# 07-NCP3066_LCD.net
KiCad netlist of a schematic drawn in Altium Designer
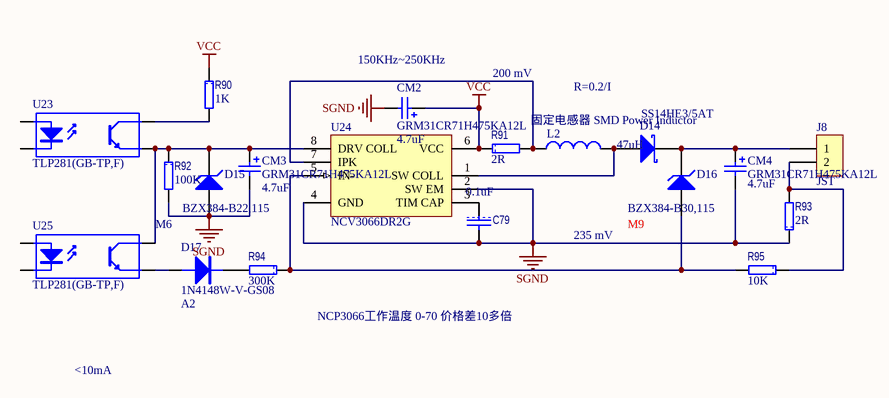
[diagram p0: 07-NCP3066_LCD背光.SchDoc]

(export (version "E")
  (design (tool "Eeschema 10.0.6"))
  (components
    (comp (ref "C79")
      (value "0.1uF")
      (footprint "1608[0603]C")
      (description "多层陶瓷电容器MLCC - SMD/SMT 0603 0.1uF 50volts X7R 10%")
      (fields (field (name "MANUFACTURER") "TDK") (field (name "MANUFACTURER PART NUMBER") "C1608X7R1H104K"))
      (libsource (lib "*") (part "CAP"))
    )
    (comp (ref "CM2")
      (value "GRM31CR71H475KA12L")
      (footprint "3216[1206]C")
      (description "多层陶瓷电容器MLCC - SMD/SMT 4.7uF 50Volts 10%")
      (fields (field (name "MANUFACTURER") "Murata Electronics") (field (name "ALTIUM_VALUE") "4.7uF"))
      (libsource (lib "Miscellaneous Devices") (part "Cap Pol2"))
    )
    (comp (ref "CM3")
      (value "GRM31CR71H475KA12L")
      (footprint "3216[1206]C")
      (description "多层陶瓷电容器MLCC - SMD/SMT 4.7uF 50Volts 10%")
      (fields (field (name "MANUFACTURER") "Murata Electronics") (field (name "ALTIUM_VALUE") "4.7uF"))
      (libsource (lib "Miscellaneous Devices") (part "Cap Pol2"))
    )
    (comp (ref "CM4")
      (value "GRM31CR71H475KA12L")
      (footprint "3216[1206]C")
      (description "多层陶瓷电容器MLCC - SMD/SMT 4.7uF 50Volts 10%")
      (fields (field (name "MANUFACTURER") "Murata Electronics") (field (name "ALTIUM_VALUE") "4.7uF"))
      (libsource (lib "Miscellaneous Devices") (part "Cap Pol2"))
    )
    (comp (ref "D14")
      (value "SS14HE3/5AT")
      (footprint "DO-214AC/SMA")
      (description "肖特基二极管与整流器 40 Volt 1.0 Amp 40 Amp IFSM")
      (fields (field (name "MANUFACTURER") "Vishay Semiconductors"))
      (libsource (lib "IR Rectifier - Schottky") (part "10BQ060"))
    )
    (comp (ref "D15")
      (value "BZX384-B22,115")
      (footprint "SOD323")
      (description "稳压二极管 DIODE ZENER 2 PCT")
      (fields (field (name "MANUFACTURER") "NXP Semiconductors") (field (name "ALTIUM_VALUE") "M6"))
      (libsource (lib "Miscellaneous Devices") (part "D Zener"))
    )
    (comp (ref "D16")
      (value "BZX384-B30,115")
      (footprint "SOD323")
      (description "稳压二极管 DIODE ZENER 2 PCT")
      (fields (field (name "MANUFACTURER") "NXP Semiconductors") (field (name "ALTIUM_VALUE") "M9"))
      (libsource (lib "Miscellaneous Devices") (part "D Zener"))
    )
    (comp (ref "D17")
      (value "1N4148W-V-GS08")
      (footprint "SOD323")
      (description "二极管 - 通用，功率，开关 100V Io/150mA")
      (fields (field (name "MANUFACTURER") "Vishay Semiconductors") (field (name "ALTIUM_VALUE") "A2"))
      (libsource (lib "IN4148") (part "1N4148W"))
    )
    (comp (ref "J8") (value "JST") (footprint "JST") (description "CON") (libsource (lib "*") (part "CON2")))
    (comp (ref "L2")
      (value "47uH")
      (footprint "INDP5050X28N")
      (description "固定电感器 SMD Power Inductor")
      (fields
        (field (name "MANUFACTURER") "Sumida")
        (field (name "MANUFACTURER PART NUMBER") "CDRH5D28RH125NP-470MC")
        (field (name "DESCRIPTION 1") "固定电感器 SMD Power Inductor")
      )
      (libsource (lib "Miscellaneous Devices") (part "Inductor"))
    )
    (comp (ref "R90")
      (value "1K")
      (footprint "1608[0603]R")
      (description "厚膜电阻器 - SMD 1/10watt 1.0Kohms 1%")
      (fields
        (field (name "MANUFACTURER") "Vishay / Dale")
        (field (name "MANUFACTURER PART NUMBER") "CRCW06031K00FKEA")
      )
      (libsource (lib "1K 1%") (part "RES"))
    )
    (comp (ref "R91")
      (value "2R")
      (footprint "1608[0603]R")
      (description "厚膜电阻器 - SMD 1/10watt 2ohms 1%")
      (fields
        (field (name "MANUFACTURER") "Vishay / Dale")
        (field (name "MANUFACTURER PART NUMBER") "CRCW06032R00FKEA")
      )
      (libsource (lib "2R 1%") (part "RES"))
    )
    (comp (ref "R92")
      (value "100K")
      (footprint "1608[0603]R")
      (description "厚膜电阻器 - SMD 1/10watt 100Kohms 1%")
      (fields
        (field (name "MANUFACTURER") "Vishay / Dale")
        (field (name "MANUFACTURER PART NUMBER") "CRCW0603100KFKEA")
      )
      (libsource (lib "100K 1%") (part "RES"))
    )
    (comp (ref "R93")
      (value "2R")
      (footprint "1608[0603]R")
      (description "厚膜电阻器 - SMD 1/10watt 2ohms 1%")
      (fields
        (field (name "MANUFACTURER") "Vishay / Dale")
        (field (name "MANUFACTURER PART NUMBER") "CRCW06032R00FKEA")
      )
      (libsource (lib "2R 1%") (part "RES"))
    )
    (comp (ref "R94")
      (value "300K")
      (footprint "1608[0603]R")
      (description "厚膜电阻器 - SMD 1/10watt 300Kohms 1%")
      (fields
        (field (name "MANUFACTURER") "Vishay / Dale")
        (field (name "MANUFACTURER PART NUMBER") "CRCW0603300KFKEA")
      )
      (libsource (lib "300K 1%") (part "RES"))
    )
    (comp (ref "R95")
      (value "10K")
      (footprint "1608[0603]R")
      (description "厚膜电阻器 - SMD 1/10watt 10Kohms 1%")
      (fields
        (field (name "MANUFACTURER") "Vishay / Dale")
        (field (name "MANUFACTURER PART NUMBER") "CRCW060310K0FKEA")
      )
      (libsource (lib "10K 1%") (part "RES"))
    )
    (comp (ref "U23")
      (value "TLP281(GB-TP,F)")
      (footprint "SSOP4_N")
      (description "晶体管输出光电耦合器 80Vceo 2500Vrms standard")
      (fields (field (name "MANUFACTURER") "Toshiba"))
      (libsource (lib "Miscellaneous Devices") (part "Optoisolator1"))
    )
    (comp (ref "U24")
      (value "NCV3066DR2G")
      (footprint "SOIC8_N")
      (description "IC LED DRIVER HIGH BRIGHT 8-SOIC")
      (fields (field (name "MANUFACTURER") "ON Semiconductor"))
      (libsource (lib "ON Semi Power Mgt DC-DC Converter") (part "MC33063AD"))
    )
    (comp (ref "U25")
      (value "TLP281(GB-TP,F)")
      (footprint "SSOP4_N")
      (description "晶体管输出光电耦合器 80Vceo 2500Vrms standard")
      (fields (field (name "MANUFACTURER") "Toshiba"))
      (libsource (lib "Miscellaneous Devices") (part "Optoisolator1"))
    )
  )
  (nets
    (net (code "1") (name "Net-(D14-A)") (class "Default")
      (node (ref "D14") (pin "1") (pinfunction "A_1") (pintype "passive"))
      (node (ref "L2") (pin "2") (pinfunction "2_2") (pintype "passive"))
      (node (ref "U24") (pin "1") (pinfunction "SW_COLL_1") (pintype "passive"))
    )
    (net (code "2") (name "Net-(D14-K)") (class "Default")
      (node (ref "CM4") (pin "1") (pinfunction "1_1") (pintype "passive"))
      (node (ref "D14") (pin "2") (pinfunction "K_2") (pintype "passive"))
      (node (ref "D16") (pin "2") (pinfunction "K_2") (pintype "passive"))
      (node (ref "J8") (pin "1") (pinfunction "1_1") (pintype "passive"))
    )
    (net (code "3") (name "Net-(D15-K)") (class "Default")
      (node (ref "CM3") (pin "1") (pinfunction "1_1") (pintype "passive"))
      (node (ref "D15") (pin "2") (pinfunction "K_2") (pintype "passive"))
      (node (ref "R92") (pin "1") (pinfunction "1_1") (pintype "passive"))
      (node (ref "U23") (pin "3") (pinfunction "E_3") (pintype "passive"))
      (node (ref "U24") (pin "8") (pinfunction "DRV_COLL_8") (pintype "open_collector"))
      (node (ref "U25") (pin "4") (pinfunction "C_4") (pintype "passive"))
    )
    (net (code "4") (name "Net-(D16-A)") (class "Default")
      (node (ref "D16") (pin "1") (pinfunction "A_1") (pintype "passive"))
      (node (ref "R94") (pin "1") (pinfunction "1_1") (pintype "passive"))
      (node (ref "R95") (pin "2") (pinfunction "2_2") (pintype "passive"))
      (node (ref "U24") (pin "5") (pinfunction "IN-_5") (pintype "input"))
    )
    (net (code "5") (name "Net-(D17-A)") (class "Default")
      (node (ref "D17") (pin "1") (pinfunction "A_1") (pintype "passive"))
      (node (ref "U25") (pin "3") (pinfunction "E_3") (pintype "passive"))
    )
    (net (code "6") (name "Net-(D17-K)") (class "Default")
      (node (ref "D17") (pin "2") (pinfunction "K_2") (pintype "passive"))
      (node (ref "R94") (pin "2") (pinfunction "2_2") (pintype "passive"))
    )
    (net (code "7") (name "Net-(J8-Pad2)") (class "Default")
      (node (ref "J8") (pin "2") (pinfunction "2_2") (pintype "passive"))
      (node (ref "R93") (pin "2") (pinfunction "2_2") (pintype "passive"))
      (node (ref "R95") (pin "1") (pinfunction "1_1") (pintype "passive"))
    )
    (net (code "8") (name "Net-(U23-C)") (class "Default")
      (node (ref "R90") (pin "2") (pinfunction "2_2") (pintype "passive"))
      (node (ref "U23") (pin "4") (pinfunction "C_4") (pintype "passive"))
    )
    (net (code "9") (name "Net-(U24-IPK)") (class "Default")
      (node (ref "L2") (pin "1") (pinfunction "1_1") (pintype "passive"))
      (node (ref "R91") (pin "2") (pinfunction "2_2") (pintype "passive"))
      (node (ref "U24") (pin "7") (pinfunction "IPK_7") (pintype "passive"))
    )
    (net (code "10") (name "Net-(U24-TIM_CAP)") (class "Default")
      (node (ref "C79") (pin "1") (pinfunction "1_1") (pintype "passive"))
      (node (ref "U24") (pin "3") (pinfunction "TIM_CAP_3") (pintype "passive"))
    )
    (net (code "11") (name "SGND") (class "Default")
      (node (ref "C79") (pin "2") (pinfunction "2_2") (pintype "passive"))
      (node (ref "CM2") (pin "2") (pinfunction "2_2") (pintype "passive"))
      (node (ref "CM3") (pin "2") (pinfunction "2_2") (pintype "passive"))
      (node (ref "CM4") (pin "2") (pinfunction "2_2") (pintype "passive"))
      (node (ref "D15") (pin "1") (pinfunction "A_1") (pintype "passive"))
      (node (ref "R92") (pin "2") (pinfunction "2_2") (pintype "passive"))
      (node (ref "R93") (pin "1") (pinfunction "1_1") (pintype "passive"))
      (node (ref "U24") (pin "2") (pinfunction "SW_EM_2") (pintype "passive"))
      (node (ref "U24") (pin "4") (pinfunction "GND_4") (pintype "power_in"))
    )
    (net (code "12") (name "VCC") (class "Default")
      (node (ref "CM2") (pin "1") (pinfunction "1_1") (pintype "passive"))
      (node (ref "R90") (pin "1") (pinfunction "1_1") (pintype "passive"))
      (node (ref "R91") (pin "1") (pinfunction "1_1") (pintype "passive"))
      (node (ref "U24") (pin "6") (pinfunction "VCC_6") (pintype "power_in"))
    )
    (net (code "13") (name "unconnected-(U23-A-Pad1)") (class "Default")
      (node (ref "U23") (pin "1") (pinfunction "A_1") (pintype "passive"))
    )
    (net (code "14") (name "unconnected-(U23-K-Pad2)") (class "Default")
      (node (ref "U23") (pin "2") (pinfunction "K_2") (pintype "passive"))
    )
    (net (code "15") (name "unconnected-(U25-A-Pad1)") (class "Default")
      (node (ref "U25") (pin "1") (pinfunction "A_1") (pintype "passive"))
    )
    (net (code "16") (name "unconnected-(U25-K-Pad2)") (class "Default")
      (node (ref "U25") (pin "2") (pinfunction "K_2") (pintype "passive"))
    )
  )
)
